# Power.net
KiCad netlist of a schematic drawn in Altium Designer
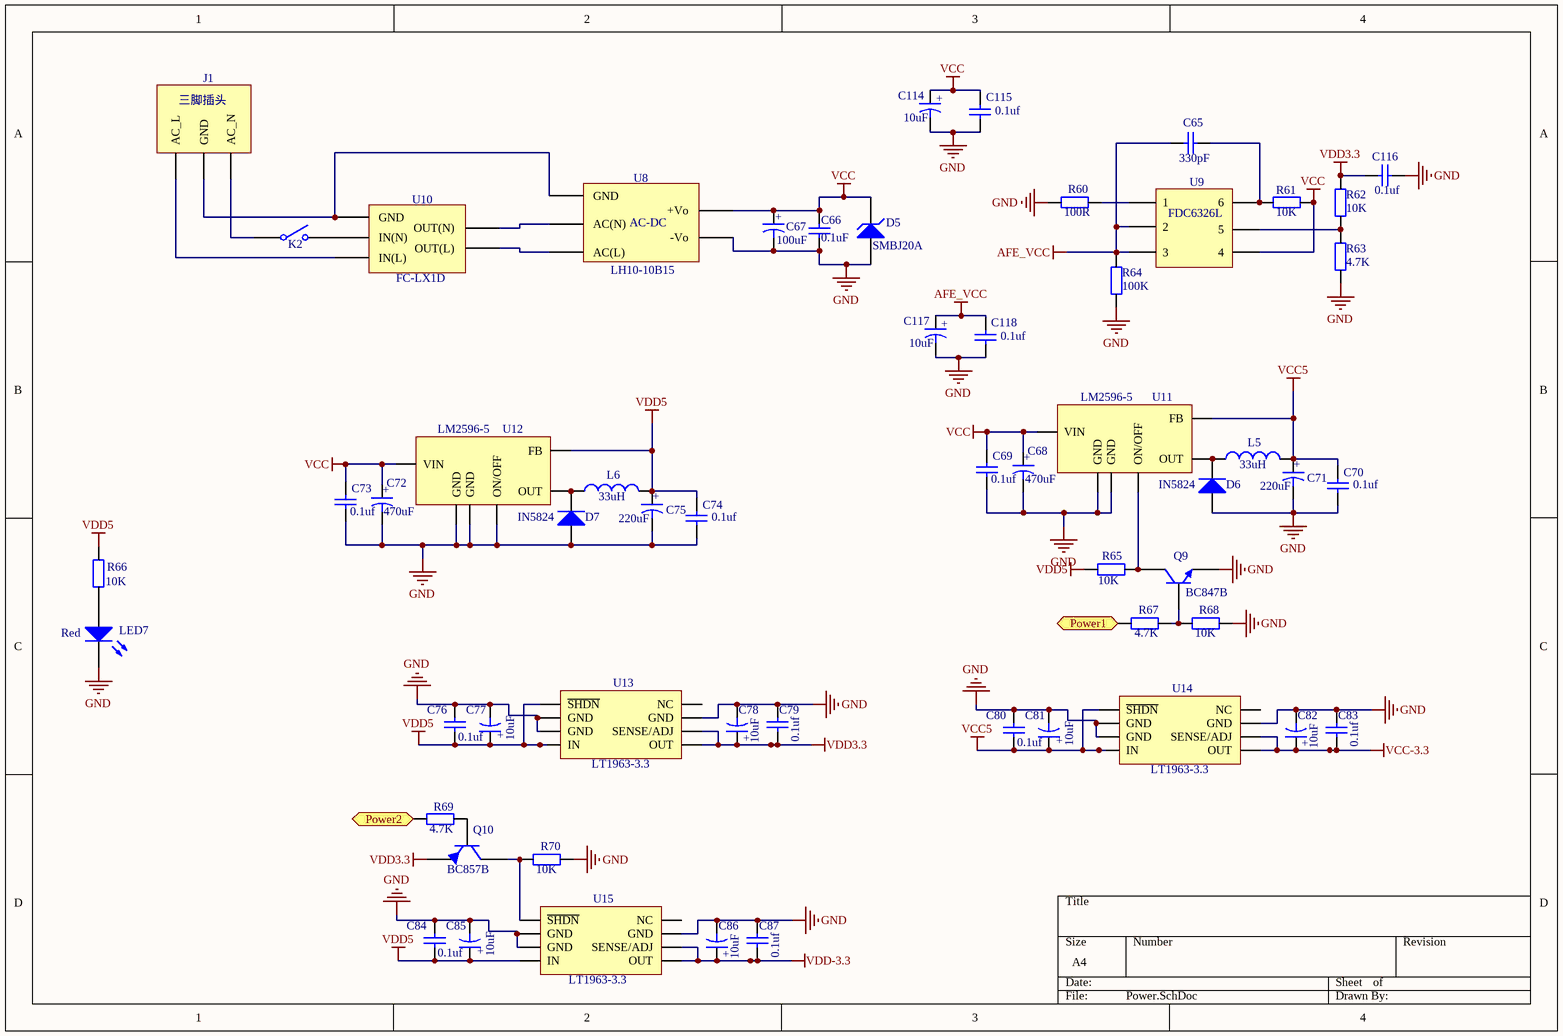
[diagram p0: Power.SchDoc]

(export (version "E")
  (design (tool "Eeschema 10.0.6"))
  (components
    (comp (ref "C65")
      (value "330pF")
      (footprint "0805")
      (fields (field (name "Comment") "Capacitor-0805"))
      (libsource (lib "集成库—大岐") (part "Capacitor-0805"))
    )
    (comp (ref "C66")
      (value "0.1uF")
      (footprint "0805")
      (fields (field (name "Comment") "Capacitor-0805"))
      (libsource (lib "原理图库") (part "Capacitor-0805"))
    )
    (comp (ref "C67")
      (value "100uF")
      (footprint "贴片铝电容-8*10.3")
      (fields (field (name "ALTIUM_UNNAMED_1") "+") (field (name "Comment") "电解电容"))
      (libsource (lib "原理图库") (part "电解电容"))
    )
    (comp (ref "C68")
      (value "470uF")
      (footprint "贴片铝电容-10*10")
      (fields (field (name "ALTIUM_UNNAMED_1") "+") (field (name "Comment") "电解电容"))
      (libsource (lib "集成库—大岐") (part "电解电容"))
    )
    (comp (ref "C69")
      (value "0.1uf")
      (footprint "0805")
      (fields (field (name "Comment") "Capacitor-0805"))
      (libsource (lib "集成库—大岐") (part "Capacitor-0805"))
    )
    (comp (ref "C70")
      (value "0.1uf")
      (footprint "0805")
      (fields (field (name "Comment") "Capacitor-0805"))
      (libsource (lib "集成库—大岐") (part "Capacitor-0805"))
    )
    (comp (ref "C71")
      (value "220uF")
      (footprint "贴片铝电容-8*10.3")
      (fields (field (name "ALTIUM_UNNAMED_1") "+") (field (name "Comment") "电解电容"))
      (libsource (lib "集成库—大岐") (part "电解电容"))
    )
    (comp (ref "C72")
      (value "470uF")
      (footprint "贴片铝电容-10*10")
      (fields (field (name "ALTIUM_UNNAMED_1") "+") (field (name "Comment") "电解电容"))
      (libsource (lib "集成库—大岐") (part "电解电容"))
    )
    (comp (ref "C73")
      (value "0.1uf")
      (footprint "0805")
      (fields (field (name "Comment") "Capacitor-0805"))
      (libsource (lib "集成库—大岐") (part "Capacitor-0805"))
    )
    (comp (ref "C74")
      (value "0.1uf")
      (footprint "0805")
      (fields (field (name "Comment") "Capacitor-0805"))
      (libsource (lib "集成库—大岐") (part "Capacitor-0805"))
    )
    (comp (ref "C75")
      (value "220uF")
      (footprint "贴片铝电容-8*10.3")
      (fields (field (name "ALTIUM_UNNAMED_1") "+") (field (name "Comment") "电解电容"))
      (libsource (lib "集成库—大岐") (part "电解电容"))
    )
    (comp (ref "C76")
      (value "0.1uf")
      (footprint "0805")
      (fields (field (name "Comment") "Capacitor-0805"))
      (libsource (lib "集成库—大岐") (part "Capacitor-0805"))
    )
    (comp (ref "C77")
      (value "10uF")
      (footprint "钽电容1206（A3216）")
      (fields (field (name "ALTIUM_UNNAMED_1") "+") (field (name "Comment") "电解电容"))
      (libsource (lib "集成库—大岐") (part "电解电容"))
    )
    (comp (ref "C78")
      (value "10uF")
      (footprint "钽电容1206（A3216）")
      (fields (field (name "ALTIUM_UNNAMED_1") "+") (field (name "Comment") "电解电容"))
      (libsource (lib "集成库—大岐") (part "电解电容"))
    )
    (comp (ref "C79")
      (value "0.1uf")
      (footprint "0805")
      (fields (field (name "Comment") "Capacitor-0805"))
      (libsource (lib "集成库—大岐") (part "Capacitor-0805"))
    )
    (comp (ref "C80")
      (value "0.1uf")
      (footprint "0805")
      (fields (field (name "Comment") "Capacitor-0805"))
      (libsource (lib "集成库—大岐") (part "Capacitor-0805"))
    )
    (comp (ref "C81")
      (value "10uF")
      (footprint "钽电容1206（A3216）")
      (fields (field (name "ALTIUM_UNNAMED_1") "+") (field (name "Comment") "电解电容"))
      (libsource (lib "集成库—大岐") (part "电解电容"))
    )
    (comp (ref "C82")
      (value "10uF")
      (footprint "钽电容1206（A3216）")
      (fields (field (name "ALTIUM_UNNAMED_1") "+") (field (name "Comment") "电解电容"))
      (libsource (lib "集成库—大岐") (part "电解电容"))
    )
    (comp (ref "C83")
      (value "0.1uf")
      (footprint "0805")
      (fields (field (name "Comment") "Capacitor-0805"))
      (libsource (lib "集成库—大岐") (part "Capacitor-0805"))
    )
    (comp (ref "C84")
      (value "0.1uf")
      (footprint "0805")
      (fields (field (name "Comment") "Capacitor-0805"))
      (libsource (lib "集成库—大岐") (part "Capacitor-0805"))
    )
    (comp (ref "C85")
      (value "10uF")
      (footprint "钽电容1206（A3216）")
      (fields (field (name "ALTIUM_UNNAMED_1") "+") (field (name "Comment") "电解电容"))
      (libsource (lib "集成库—大岐") (part "电解电容"))
    )
    (comp (ref "C86")
      (value "10uF")
      (footprint "钽电容1206（A3216）")
      (fields (field (name "ALTIUM_UNNAMED_1") "+") (field (name "Comment") "电解电容"))
      (libsource (lib "集成库—大岐") (part "电解电容"))
    )
    (comp (ref "C87")
      (value "0.1uf")
      (footprint "0805")
      (fields (field (name "Comment") "Capacitor-0805"))
      (libsource (lib "集成库—大岐") (part "Capacitor-0805"))
    )
    (comp (ref "C114")
      (value "10uF")
      (footprint "3528")
      (fields (field (name "ALTIUM_UNNAMED_1") "+") (field (name "Comment") "电解电容"))
      (libsource (lib "原理图库") (part "电解电容"))
    )
    (comp (ref "C115")
      (value "0.1uf")
      (footprint "0805")
      (fields (field (name "Comment") "Capacitor-0805"))
      (libsource (lib "集成库—大岐") (part "Capacitor-0805"))
    )
    (comp (ref "C116")
      (value "0.1uf")
      (footprint "0603")
      (fields (field (name "Comment") "Capacitor-0805"))
      (libsource (lib "集成库—大岐") (part "Capacitor-0805"))
    )
    (comp (ref "C117")
      (value "10uF")
      (footprint "3528")
      (fields (field (name "ALTIUM_UNNAMED_1") "+") (field (name "Comment") "电解电容"))
      (libsource (lib "原理图库") (part "电解电容"))
    )
    (comp (ref "C118")
      (value "0.1uf")
      (footprint "0805")
      (fields (field (name "Comment") "Capacitor-0805"))
      (libsource (lib "集成库—大岐") (part "Capacitor-0805"))
    )
    (comp (ref "D5")
      (value "SMBJ20A")
      (footprint "SMBJ20A")
      (fields (field (name "NAME") "SMBJ20A"))
      (libsource (lib "原理图库") (part "SMBJ20A"))
    )
    (comp (ref "D6")
      (value "IN5824")
      (footprint "IN5824")
      (fields (field (name "ALTIUM_UNNAMED_1") "IN5824"))
      (libsource (lib "集成库—大岐") (part "IN5824"))
    )
    (comp (ref "D7")
      (value "IN5824")
      (footprint "IN5824")
      (fields (field (name "ALTIUM_UNNAMED_1") "IN5824"))
      (libsource (lib "集成库—大岐") (part "IN5824"))
    )
    (comp (ref "J1")
      (value "三脚插头")
      (footprint "三芯蛙座")
      (fields (field (name "NAME") "三脚插头"))
      (libsource (lib "原理图库") (part "三脚插头"))
    )
    (comp (ref "K2") (value "开关") (footprint "T型接头") (libsource (lib "原理图库") (part "开关")))
    (comp (ref "L5")
      (value "33uH")
      (footprint "SLF6025   电感")
      (fields (field (name "Comment") "Inductor"))
      (libsource (lib "集成库—大岐") (part "Inductor"))
    )
    (comp (ref "L6")
      (value "33uH")
      (footprint "SLF6025   电感")
      (fields (field (name "Comment") "Inductor"))
      (libsource (lib "集成库—大岐") (part "Inductor"))
    )
    (comp (ref "LED7")
      (value "LED")
      (footprint "外插小灯")
      (fields (field (name "COLOR") "Red"))
      (libsource (lib "原理图库") (part "LED"))
    )
    (comp (ref "Q9")
      (value "BC847")
      (footprint "BC847B")
      (fields (field (name "NAME") "BC847B"))
      (libsource (lib "原理图库") (part "BC847"))
    )
    (comp (ref "Q10")
      (value "BC587B")
      (footprint "BC847B")
      (fields (field (name "NAME") "BC857B"))
      (libsource (lib "原理图库") (part "BC587B"))
    )
    (comp (ref "R60")
      (value "100R")
      (footprint "0603")
      (fields (field (name "Comment") "Resistor-0603"))
      (libsource (lib "") (part "Resistor-0603_2"))
    )
    (comp (ref "R61")
      (value "10K")
      (footprint "0603")
      (fields (field (name "Comment") "Resistor-0603"))
      (libsource (lib "原理图库") (part "Resistor-0603"))
    )
    (comp (ref "R62")
      (value "10K")
      (footprint "0603")
      (fields (field (name "Comment") "Resistor-0603"))
      (libsource (lib "") (part "Resistor-0603_1"))
    )
    (comp (ref "R63")
      (value "4.7K")
      (footprint "0603")
      (fields (field (name "Comment") "Resistor-0603"))
      (libsource (lib "") (part "Resistor-0603_1"))
    )
    (comp (ref "R64")
      (value "100K")
      (footprint "0603")
      (fields (field (name "Comment") "Resistor-0603"))
      (libsource (lib "") (part "Resistor-0603_1"))
    )
    (comp (ref "R65")
      (value "10K")
      (footprint "0603")
      (fields (field (name "Comment") "Resistor-0603"))
      (libsource (lib "") (part "Resistor-0603_2"))
    )
    (comp (ref "R66")
      (value "10K")
      (footprint "0603")
      (fields (field (name "Comment") "Resistor-0603"))
      (libsource (lib "") (part "Resistor-0603_1"))
    )
    (comp (ref "R67")
      (value "4.7K")
      (footprint "0603")
      (fields (field (name "Comment") "Resistor-0603"))
      (libsource (lib "原理图库") (part "Resistor-0603"))
    )
    (comp (ref "R68")
      (value "10K")
      (footprint "0603")
      (fields (field (name "Comment") "Resistor-0603"))
      (libsource (lib "原理图库") (part "Resistor-0603"))
    )
    (comp (ref "R69")
      (value "4.7K")
      (footprint "0603")
      (fields (field (name "Comment") "Resistor-0603"))
      (libsource (lib "原理图库") (part "Resistor-0603"))
    )
    (comp (ref "R70")
      (value "10K")
      (footprint "0603")
      (fields (field (name "Comment") "Resistor-0603"))
      (libsource (lib "原理图库") (part "Resistor-0603"))
    )
    (comp (ref "U8")
      (value "LH10-10B15")
      (footprint "LH10-10B15")
      (fields (field (name "DESCRIBE") "AC-DC") (field (name "NAME") "LH10-10B15"))
      (libsource (lib "原理图库") (part "LH10-10B15"))
    )
    (comp (ref "U9")
      (value "FDC6326L")
      (footprint "FDC6326L")
      (fields (field (name "NAME") "FDC6326L"))
      (libsource (lib "原理图库") (part "FDC6326L"))
    )
    (comp (ref "U10")
      (value "FC-LX1D")
      (footprint "FC-LX1D")
      (fields (field (name "NAME") "FC-LX1D"))
      (libsource (lib "原理图库") (part "FC-LX1D"))
    )
    (comp (ref "U11")
      (value "LM2596")
      (footprint "LM2596")
      (fields (field (name "ALTIUM_UNNAMED_1") "LM2596-5"))
      (libsource (lib "集成库—大岐") (part "LM2596"))
    )
    (comp (ref "U12")
      (value "LM2596")
      (footprint "LM2596")
      (fields (field (name "ALTIUM_UNNAMED_1") "LM2596-5"))
      (libsource (lib "集成库—大岐") (part "LM2596"))
    )
    (comp (ref "U13")
      (value "LT1963")
      (footprint "LT1963")
      (fields (field (name "ALTIUM_UNNAMED_1") "LT1963-3.3"))
      (libsource (lib "集成库—大岐") (part "LT1963"))
    )
    (comp (ref "U14")
      (value "LT1963")
      (footprint "LT1963")
      (fields (field (name "ALTIUM_UNNAMED_1") "LT1963-3.3"))
      (libsource (lib "集成库—大岐") (part "LT1963"))
    )
    (comp (ref "U15")
      (value "LT1963")
      (footprint "LT1963")
      (fields (field (name "ALTIUM_UNNAMED_1") "LT1963-3.3"))
      (libsource (lib "集成库—大岐") (part "LT1963"))
    )
  )
  (nets
    (net (code "1") (name "/Power1") (class "Default")
      (node (ref "R67") (pin "2") (pinfunction "2_2") (pintype "passive"))
    )
    (net (code "2") (name "/Power2") (class "Default")
      (node (ref "R69") (pin "2") (pinfunction "2_2") (pintype "passive"))
    )
    (net (code "3") (name "AFE_VCC") (class "Default")
      (node (ref "C117") (pin "2") (pinfunction "2_2") (pintype "passive"))
      (node (ref "C118") (pin "2") (pinfunction "2_2") (pintype "passive"))
      (node (ref "C65") (pin "2") (pinfunction "2_2") (pintype "passive"))
      (node (ref "R64") (pin "2") (pinfunction "2_2") (pintype "passive"))
      (node (ref "U9") (pin "2") (pinfunction "2_2") (pintype "passive"))
      (node (ref "U9") (pin "3") (pinfunction "3_3") (pintype "passive"))
    )
    (net (code "4") (name "GND") (class "Default")
      (node (ref "C114") (pin "1") (pinfunction "1_1") (pintype "passive"))
      (node (ref "C115") (pin "1") (pinfunction "1_1") (pintype "passive"))
      (node (ref "C116") (pin "1") (pinfunction "1_1") (pintype "passive"))
      (node (ref "C117") (pin "1") (pinfunction "1_1") (pintype "passive"))
      (node (ref "C118") (pin "1") (pinfunction "1_1") (pintype "passive"))
      (node (ref "C66") (pin "1") (pinfunction "1_1") (pintype "passive"))
      (node (ref "C67") (pin "1") (pinfunction "1_1") (pintype "passive"))
      (node (ref "C68") (pin "1") (pinfunction "1_1") (pintype "passive"))
      (node (ref "C69") (pin "1") (pinfunction "1_1") (pintype "passive"))
      (node (ref "C70") (pin "1") (pinfunction "1_1") (pintype "passive"))
      (node (ref "C71") (pin "1") (pinfunction "1_1") (pintype "passive"))
      (node (ref "C72") (pin "1") (pinfunction "1_1") (pintype "passive"))
      (node (ref "C73") (pin "1") (pinfunction "1_1") (pintype "passive"))
      (node (ref "C74") (pin "1") (pinfunction "1_1") (pintype "passive"))
      (node (ref "C75") (pin "1") (pinfunction "1_1") (pintype "passive"))
      (node (ref "C76") (pin "2") (pinfunction "2_2") (pintype "passive"))
      (node (ref "C77") (pin "1") (pinfunction "1_1") (pintype "passive"))
      (node (ref "C78") (pin "1") (pinfunction "1_1") (pintype "passive"))
      (node (ref "C79") (pin "2") (pinfunction "2_2") (pintype "passive"))
      (node (ref "C80") (pin "2") (pinfunction "2_2") (pintype "passive"))
      (node (ref "C81") (pin "1") (pinfunction "1_1") (pintype "passive"))
      (node (ref "C82") (pin "1") (pinfunction "1_1") (pintype "passive"))
      (node (ref "C83") (pin "2") (pinfunction "2_2") (pintype "passive"))
      (node (ref "C84") (pin "2") (pinfunction "2_2") (pintype "passive"))
      (node (ref "C85") (pin "1") (pinfunction "1_1") (pintype "passive"))
      (node (ref "C86") (pin "1") (pinfunction "1_1") (pintype "passive"))
      (node (ref "C87") (pin "2") (pinfunction "2_2") (pintype "passive"))
      (node (ref "D5") (pin "1") (pinfunction "A_1") (pintype "passive"))
      (node (ref "D6") (pin "1") (pinfunction "A_1") (pintype "passive"))
      (node (ref "D7") (pin "1") (pinfunction "A_1") (pintype "passive"))
      (node (ref "LED7") (pin "2") (pinfunction "2_2") (pintype "passive"))
      (node (ref "Q9") (pin "1") (pinfunction "E_1") (pintype "passive"))
      (node (ref "R60") (pin "1") (pinfunction "1_1") (pintype "passive"))
      (node (ref "R63") (pin "1") (pinfunction "1_1") (pintype "passive"))
      (node (ref "R64") (pin "1") (pinfunction "1_1") (pintype "passive"))
      (node (ref "R68") (pin "1") (pinfunction "1_1") (pintype "passive"))
      (node (ref "R70") (pin "1") (pinfunction "1_1") (pintype "passive"))
      (node (ref "U11") (pin "3") (pinfunction "GND_3") (pintype "passive"))
      (node (ref "U11") (pin "6") (pinfunction "GND_6") (pintype "passive"))
      (node (ref "U12") (pin "3") (pinfunction "GND_3") (pintype "passive"))
      (node (ref "U12") (pin "5") (pinfunction "ON/OFF_5") (pintype "passive"))
      (node (ref "U12") (pin "6") (pinfunction "GND_6") (pintype "passive"))
      (node (ref "U13") (pin "3") (pinfunction "GND_3") (pintype "passive"))
      (node (ref "U13") (pin "6") (pinfunction "GND_6") (pintype "passive"))
      (node (ref "U13") (pin "7") (pinfunction "GND_7") (pintype "passive"))
      (node (ref "U14") (pin "3") (pinfunction "GND_3") (pintype "passive"))
      (node (ref "U14") (pin "6") (pinfunction "GND_6") (pintype "passive"))
      (node (ref "U14") (pin "7") (pinfunction "GND_7") (pintype "passive"))
      (node (ref "U15") (pin "3") (pinfunction "GND_3") (pintype "passive"))
      (node (ref "U15") (pin "6") (pinfunction "GND_6") (pintype "passive"))
      (node (ref "U15") (pin "7") (pinfunction "GND_7") (pintype "passive"))
      (node (ref "U8") (pin "4") (pinfunction "-Vo_4") (pintype "passive"))
    )
    (net (code "5") (name "Net-(C65-Pad1)") (class "Default")
      (node (ref "C65") (pin "1") (pinfunction "1_1") (pintype "passive"))
      (node (ref "R61") (pin "2") (pinfunction "2_2") (pintype "passive"))
      (node (ref "U9") (pin "6") (pinfunction "6_6") (pintype "passive"))
    )
    (net (code "6") (name "Net-(D6-K)") (class "Default")
      (node (ref "D6") (pin "2") (pinfunction "K_2") (pintype "passive"))
      (node (ref "L5") (pin "1") (pinfunction "1_1") (pintype "passive"))
      (node (ref "U11") (pin "2") (pinfunction "OUT_2") (pintype "passive"))
    )
    (net (code "7") (name "Net-(D7-K)") (class "Default")
      (node (ref "D7") (pin "2") (pinfunction "K_2") (pintype "passive"))
      (node (ref "L6") (pin "1") (pinfunction "1_1") (pintype "passive"))
      (node (ref "U12") (pin "2") (pinfunction "OUT_2") (pintype "passive"))
    )
    (net (code "8") (name "Net-(J1-AC_L)") (class "Default")
      (node (ref "J1") (pin "1") (pinfunction "AC_L_1") (pintype "passive"))
      (node (ref "U10") (pin "3") (pinfunction "IN(L)_3") (pintype "passive"))
    )
    (net (code "9") (name "Net-(J1-AC_N)") (class "Default")
      (node (ref "J1") (pin "3") (pinfunction "AC_N_3") (pintype "passive"))
      (node (ref "K2") (pin "1") (pinfunction "COMMON_1") (pintype "passive"))
    )
    (net (code "10") (name "Net-(J1-GND)") (class "Default")
      (node (ref "J1") (pin "2") (pinfunction "GND_2") (pintype "passive"))
      (node (ref "U10") (pin "1") (pinfunction "GND_1") (pintype "passive"))
      (node (ref "U8") (pin "1") (pinfunction "GND_1") (pintype "passive"))
    )
    (net (code "11") (name "Net-(K2-NO)") (class "Default")
      (node (ref "K2") (pin "2") (pinfunction "NO_2") (pintype "passive"))
      (node (ref "U10") (pin "2") (pinfunction "IN(N)_2") (pintype "passive"))
    )
    (net (code "12") (name "Net-(LED7-A)") (class "Default")
      (node (ref "LED7") (pin "1") (pinfunction "A_1") (pintype "passive"))
      (node (ref "R66") (pin "1") (pinfunction "1_1") (pintype "passive"))
    )
    (net (code "13") (name "Net-(Q9-B)") (class "Default")
      (node (ref "Q9") (pin "2") (pinfunction "B_2") (pintype "passive"))
      (node (ref "R67") (pin "1") (pinfunction "1_1") (pintype "passive"))
      (node (ref "R68") (pin "2") (pinfunction "2_2") (pintype "passive"))
    )
    (net (code "14") (name "Net-(Q9-C)") (class "Default")
      (node (ref "Q9") (pin "3") (pinfunction "C_3") (pintype "passive"))
      (node (ref "R65") (pin "2") (pinfunction "2_2") (pintype "passive"))
      (node (ref "U11") (pin "5") (pinfunction "ON/OFF_5") (pintype "passive"))
    )
    (net (code "15") (name "Net-(Q10-B)") (class "Default")
      (node (ref "Q10") (pin "2") (pinfunction "B_2") (pintype "passive"))
      (node (ref "R69") (pin "1") (pinfunction "1_1") (pintype "passive"))
    )
    (net (code "16") (name "Net-(Q10-C)") (class "Default")
      (node (ref "Q10") (pin "3") (pinfunction "C_3") (pintype "passive"))
      (node (ref "R70") (pin "2") (pinfunction "2_2") (pintype "passive"))
      (node (ref "U15") (pin "5") (pinfunction "~{SHDN}_5") (pintype "passive"))
    )
    (net (code "17") (name "Net-(R60-Pad2)") (class "Default")
      (node (ref "R60") (pin "2") (pinfunction "2_2") (pintype "passive"))
      (node (ref "U9") (pin "1") (pinfunction "1_1") (pintype "passive"))
    )
    (net (code "18") (name "Net-(R62-Pad1)") (class "Default")
      (node (ref "R62") (pin "1") (pinfunction "1_1") (pintype "passive"))
      (node (ref "R63") (pin "2") (pinfunction "2_2") (pintype "passive"))
      (node (ref "U9") (pin "5") (pinfunction "5_5") (pintype "passive"))
    )
    (net (code "19") (name "Net-(U10-OUT(L))") (class "Default")
      (node (ref "U10") (pin "4") (pinfunction "OUT(L)_4") (pintype "passive"))
      (node (ref "U8") (pin "3") (pinfunction "AC(L)_3") (pintype "passive"))
    )
    (net (code "20") (name "Net-(U10-OUT(N))") (class "Default")
      (node (ref "U10") (pin "5") (pinfunction "OUT(N)_5") (pintype "passive"))
      (node (ref "U8") (pin "2") (pinfunction "AC(N)_2") (pintype "passive"))
    )
    (net (code "21") (name "VCC") (class "Default")
      (node (ref "C114") (pin "2") (pinfunction "2_2") (pintype "passive"))
      (node (ref "C115") (pin "2") (pinfunction "2_2") (pintype "passive"))
      (node (ref "C66") (pin "2") (pinfunction "2_2") (pintype "passive"))
      (node (ref "C67") (pin "2") (pinfunction "2_2") (pintype "passive"))
      (node (ref "C68") (pin "2") (pinfunction "2_2") (pintype "passive"))
      (node (ref "C69") (pin "2") (pinfunction "2_2") (pintype "passive"))
      (node (ref "C72") (pin "2") (pinfunction "2_2") (pintype "passive"))
      (node (ref "C73") (pin "2") (pinfunction "2_2") (pintype "passive"))
      (node (ref "D5") (pin "2") (pinfunction "K_2") (pintype "passive"))
      (node (ref "R61") (pin "1") (pinfunction "1_1") (pintype "passive"))
      (node (ref "U11") (pin "1") (pinfunction "VIN_1") (pintype "passive"))
      (node (ref "U12") (pin "1") (pinfunction "VIN_1") (pintype "passive"))
      (node (ref "U8") (pin "8") (pinfunction "+Vo_8") (pintype "passive"))
      (node (ref "U9") (pin "4") (pinfunction "4_4") (pintype "passive"))
    )
    (net (code "22") (name "VCC-3.3") (class "Default")
      (node (ref "C82") (pin "2") (pinfunction "2_2") (pintype "passive"))
      (node (ref "C83") (pin "1") (pinfunction "1_1") (pintype "passive"))
      (node (ref "U14") (pin "1") (pinfunction "OUT_1") (pintype "passive"))
      (node (ref "U14") (pin "2") (pinfunction "SENSE/ADJ_2") (pintype "passive"))
    )
    (net (code "23") (name "VCC5") (class "Default")
      (node (ref "C70") (pin "2") (pinfunction "2_2") (pintype "passive"))
      (node (ref "C71") (pin "2") (pinfunction "2_2") (pintype "passive"))
      (node (ref "C80") (pin "1") (pinfunction "1_1") (pintype "passive"))
      (node (ref "C81") (pin "2") (pinfunction "2_2") (pintype "passive"))
      (node (ref "L5") (pin "2") (pinfunction "2_2") (pintype "passive"))
      (node (ref "U11") (pin "4") (pinfunction "FB_4") (pintype "passive"))
      (node (ref "U14") (pin "5") (pinfunction "~{SHDN}_5") (pintype "passive"))
      (node (ref "U14") (pin "8") (pinfunction "IN_8") (pintype "passive"))
    )
    (net (code "24") (name "VDD-3.3") (class "Default")
      (node (ref "C86") (pin "2") (pinfunction "2_2") (pintype "passive"))
      (node (ref "C87") (pin "1") (pinfunction "1_1") (pintype "passive"))
      (node (ref "U15") (pin "1") (pinfunction "OUT_1") (pintype "passive"))
      (node (ref "U15") (pin "2") (pinfunction "SENSE/ADJ_2") (pintype "passive"))
    )
    (net (code "25") (name "VDD3.3") (class "Default")
      (node (ref "C116") (pin "2") (pinfunction "2_2") (pintype "passive"))
      (node (ref "C78") (pin "2") (pinfunction "2_2") (pintype "passive"))
      (node (ref "C79") (pin "1") (pinfunction "1_1") (pintype "passive"))
      (node (ref "Q10") (pin "1") (pinfunction "E_1") (pintype "passive"))
      (node (ref "R62") (pin "2") (pinfunction "2_2") (pintype "passive"))
      (node (ref "U13") (pin "1") (pinfunction "OUT_1") (pintype "passive"))
      (node (ref "U13") (pin "2") (pinfunction "SENSE/ADJ_2") (pintype "passive"))
    )
    (net (code "26") (name "VDD5") (class "Default")
      (node (ref "C74") (pin "2") (pinfunction "2_2") (pintype "passive"))
      (node (ref "C75") (pin "2") (pinfunction "2_2") (pintype "passive"))
      (node (ref "C76") (pin "1") (pinfunction "1_1") (pintype "passive"))
      (node (ref "C77") (pin "2") (pinfunction "2_2") (pintype "passive"))
      (node (ref "C84") (pin "1") (pinfunction "1_1") (pintype "passive"))
      (node (ref "C85") (pin "2") (pinfunction "2_2") (pintype "passive"))
      (node (ref "L6") (pin "2") (pinfunction "2_2") (pintype "passive"))
      (node (ref "R65") (pin "1") (pinfunction "1_1") (pintype "passive"))
      (node (ref "R66") (pin "2") (pinfunction "2_2") (pintype "passive"))
      (node (ref "U12") (pin "4") (pinfunction "FB_4") (pintype "passive"))
      (node (ref "U13") (pin "5") (pinfunction "~{SHDN}_5") (pintype "passive"))
      (node (ref "U13") (pin "8") (pinfunction "IN_8") (pintype "passive"))
      (node (ref "U15") (pin "8") (pinfunction "IN_8") (pintype "passive"))
    )
    (net (code "27") (name "unconnected-(U13-NC-Pad4)") (class "Default")
      (node (ref "U13") (pin "4") (pinfunction "NC_4") (pintype "passive"))
    )
    (net (code "28") (name "unconnected-(U14-NC-Pad4)") (class "Default")
      (node (ref "U14") (pin "4") (pinfunction "NC_4") (pintype "passive"))
    )
    (net (code "29") (name "unconnected-(U15-NC-Pad4)") (class "Default")
      (node (ref "U15") (pin "4") (pinfunction "NC_4") (pintype "passive"))
    )
  )
)
